# TK510_Signalbakplan.net
KiCad netlist of a schematic drawn in Altium Designer
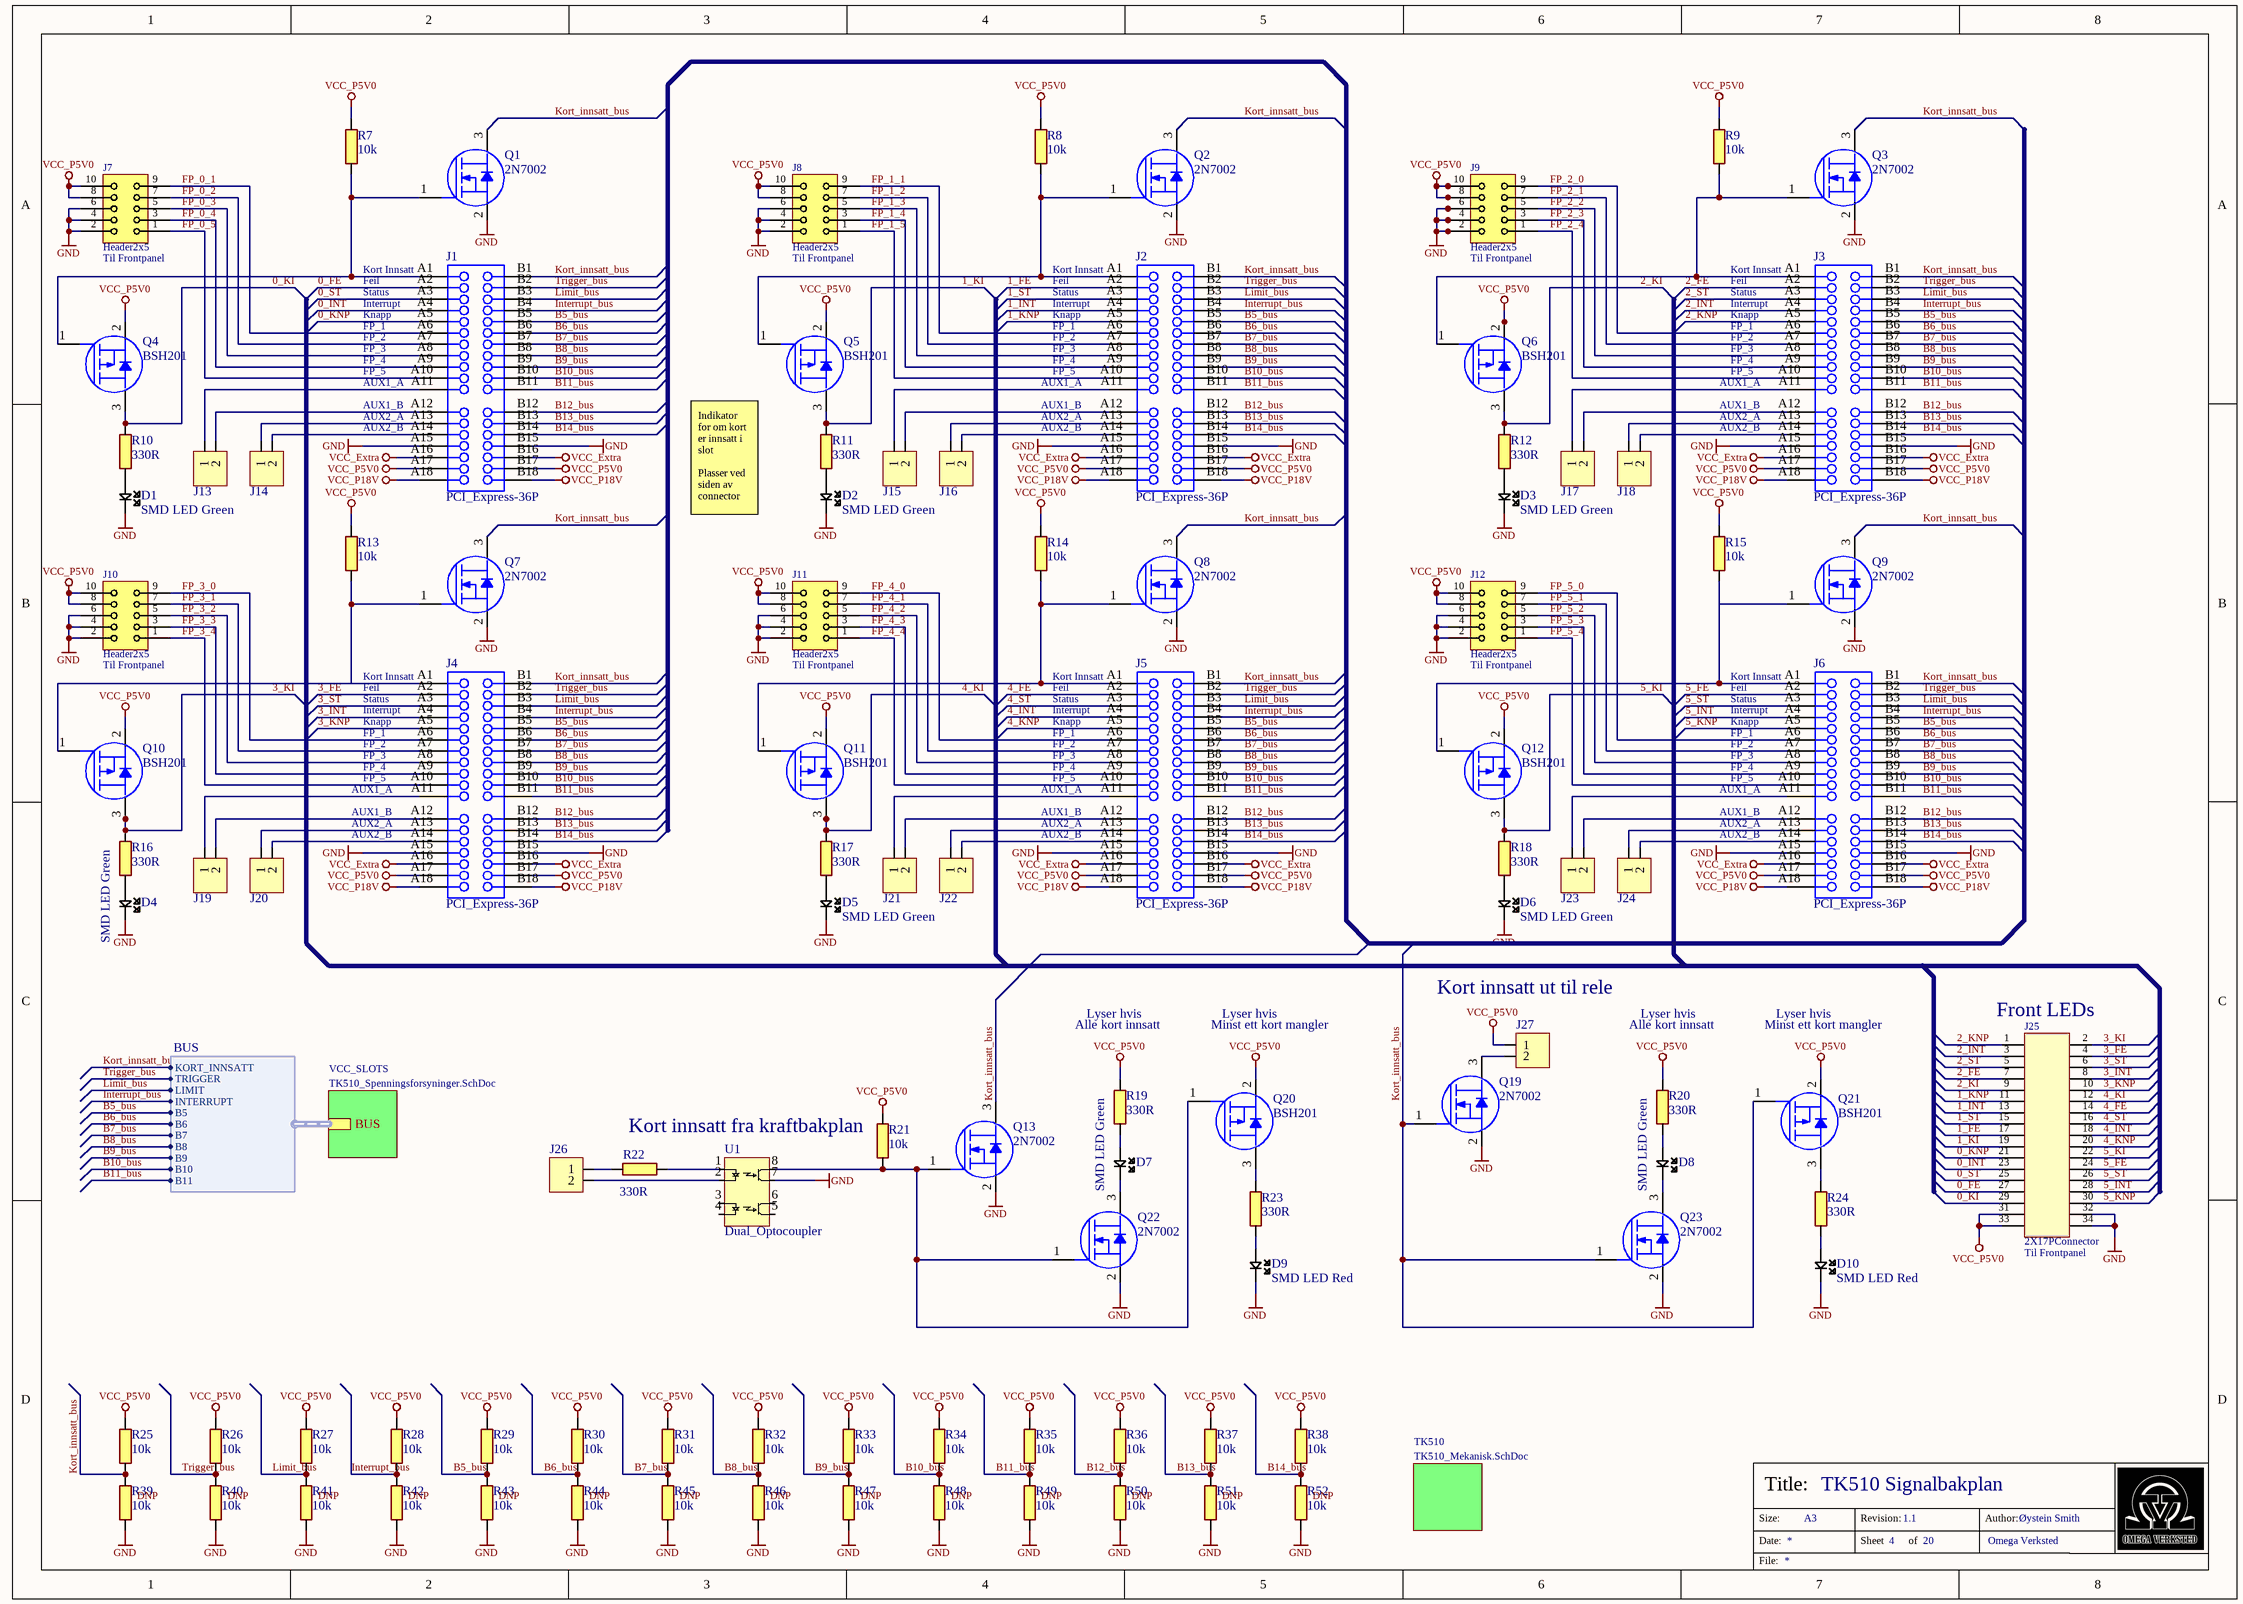
[diagram p0: TK510_Signalbakplan.SchDoc]

(export (version "E")
  (design (tool "Eeschema 10.0.6"))
  (components
    (comp (ref "D1")
      (value "SMD LED Green")
      (footprint "I_LEDC0603(1608)_N")
      (description "SMD")
      (libsource (lib "OVLib_64") (part "LED"))
    )
    (comp (ref "D2")
      (value "SMD LED Green")
      (footprint "I_LEDC0603(1608)_N")
      (description "SMD")
      (libsource (lib "OVLib_64") (part "LED"))
    )
    (comp (ref "D3")
      (value "SMD LED Green")
      (footprint "I_LEDC0603(1608)_N")
      (description "SMD")
      (libsource (lib "OVLib_64") (part "LED"))
    )
    (comp (ref "D4")
      (value "SMD LED Green")
      (footprint "I_LEDC0603(1608)_N")
      (description "SMD")
      (libsource (lib "OVLib_64") (part "LED"))
    )
    (comp (ref "D5")
      (value "SMD LED Green")
      (footprint "I_LEDC0603(1608)_N")
      (description "SMD")
      (libsource (lib "OVLib_64") (part "LED"))
    )
    (comp (ref "D6")
      (value "SMD LED Green")
      (footprint "I_LEDC0603(1608)_N")
      (description "SMD")
      (libsource (lib "OVLib_64") (part "LED"))
    )
    (comp (ref "D7")
      (value "SMD LED Green")
      (footprint "I_LEDC0603(1608)_N")
      (description "SMD")
      (libsource (lib "OVLib_64") (part "LED"))
    )
    (comp (ref "D8")
      (value "SMD LED Green")
      (footprint "I_LEDC0603(1608)_N")
      (description "SMD")
      (libsource (lib "OVLib_64") (part "LED"))
    )
    (comp (ref "D9")
      (value "SMD LED Red")
      (footprint "I_LEDC0603(1608)_N")
      (description "SMD")
      (libsource (lib "OVLib_64") (part "LED"))
    )
    (comp (ref "D10")
      (value "SMD LED Red")
      (footprint "I_LEDC0603(1608)_N")
      (description "SMD")
      (libsource (lib "OVLib_64") (part "LED"))
    )
    (comp (ref "J1")
      (value "PCI_Express-36P")
      (footprint "PCI_Express-36P")
      (libsource (lib "OVLib_64") (part "PCI_Express-36P"))
    )
    (comp (ref "J2")
      (value "PCI_Express-36P")
      (footprint "PCI_Express-36P")
      (libsource (lib "OVLib_64") (part "PCI_Express-36P"))
    )
    (comp (ref "J3")
      (value "PCI_Express-36P")
      (footprint "PCI_Express-36P")
      (libsource (lib "OVLib_64") (part "PCI_Express-36P"))
    )
    (comp (ref "J4")
      (value "PCI_Express-36P")
      (footprint "PCI_Express-36P")
      (libsource (lib "OVLib_64") (part "PCI_Express-36P"))
    )
    (comp (ref "J5")
      (value "PCI_Express-36P")
      (footprint "PCI_Express-36P")
      (libsource (lib "OVLib_64") (part "PCI_Express-36P"))
    )
    (comp (ref "J6")
      (value "PCI_Express-36P")
      (footprint "PCI_Express-36P")
      (libsource (lib "OVLib_64") (part "PCI_Express-36P"))
    )
    (comp (ref "J7")
      (value "Header2x5")
      (footprint "HDRV10W64P254_2X5_2030X900X900B")
      (description "Header")
      (libsource (lib "OVLib_64") (part "Header2x5"))
    )
    (comp (ref "J8")
      (value "Header2x5")
      (footprint "HDRV10W64P254_2X5_2030X900X900B")
      (description "Header")
      (libsource (lib "OVLib_64") (part "Header2x5"))
    )
    (comp (ref "J9")
      (value "Header2x5")
      (footprint "HDRV10W64P254_2X5_2030X900X900B")
      (description "Header")
      (libsource (lib "OVLib_64") (part "Header2x5"))
    )
    (comp (ref "J10")
      (value "Header2x5")
      (footprint "HDRV10W64P254_2X5_2030X900X900B")
      (description "Header")
      (libsource (lib "OVLib_64") (part "Header2x5"))
    )
    (comp (ref "J11")
      (value "Header2x5")
      (footprint "HDRV10W64P254_2X5_2030X900X900B")
      (description "Header")
      (libsource (lib "OVLib_64") (part "Header2x5"))
    )
    (comp (ref "J12")
      (value "Header2x5")
      (footprint "HDRV10W64P254_2X5_2030X900X900B")
      (description "Header")
      (libsource (lib "OVLib_64") (part "Header2x5"))
    )
    (comp (ref "J13")
      (value "B2B-XH-A (LF)(SN)")
      (footprint "JST_2P")
      (description "JST 2pin (pris pr. stk.)")
      (libsource (lib "OVLib_64") (part "2PConnector"))
    )
    (comp (ref "J14")
      (value "B2B-XH-A (LF)(SN)")
      (footprint "JST_2P")
      (description "JST 2pin (pris pr. stk.)")
      (libsource (lib "OVLib_64") (part "2PConnector"))
    )
    (comp (ref "J15")
      (value "B2B-XH-A (LF)(SN)")
      (footprint "JST_2P")
      (description "JST 2pin (pris pr. stk.)")
      (libsource (lib "OVLib_64") (part "2PConnector"))
    )
    (comp (ref "J16")
      (value "B2B-XH-A (LF)(SN)")
      (footprint "JST_2P")
      (description "JST 2pin (pris pr. stk.)")
      (libsource (lib "OVLib_64") (part "2PConnector"))
    )
    (comp (ref "J17")
      (value "B2B-XH-A (LF)(SN)")
      (footprint "JST_2P")
      (description "JST 2pin (pris pr. stk.)")
      (libsource (lib "OVLib_64") (part "2PConnector"))
    )
    (comp (ref "J18")
      (value "B2B-XH-A (LF)(SN)")
      (footprint "JST_2P")
      (description "JST 2pin (pris pr. stk.)")
      (libsource (lib "OVLib_64") (part "2PConnector"))
    )
    (comp (ref "J19")
      (value "B2B-XH-A (LF)(SN)")
      (footprint "JST_2P")
      (description "JST 2pin (pris pr. stk.)")
      (libsource (lib "OVLib_64") (part "2PConnector"))
    )
    (comp (ref "J20")
      (value "B2B-XH-A (LF)(SN)")
      (footprint "JST_2P")
      (description "JST 2pin (pris pr. stk.)")
      (libsource (lib "OVLib_64") (part "2PConnector"))
    )
    (comp (ref "J21")
      (value "B2B-XH-A (LF)(SN)")
      (footprint "JST_2P")
      (description "JST 2pin (pris pr. stk.)")
      (libsource (lib "OVLib_64") (part "2PConnector"))
    )
    (comp (ref "J22")
      (value "B2B-XH-A (LF)(SN)")
      (footprint "JST_2P")
      (description "JST 2pin (pris pr. stk.)")
      (libsource (lib "OVLib_64") (part "2PConnector"))
    )
    (comp (ref "J23")
      (value "B2B-XH-A (LF)(SN)")
      (footprint "JST_2P")
      (description "JST 2pin (pris pr. stk.)")
      (libsource (lib "OVLib_64") (part "2PConnector"))
    )
    (comp (ref "J24")
      (value "B2B-XH-A (LF)(SN)")
      (footprint "JST_2P")
      (description "JST 2pin (pris pr. stk.)")
      (libsource (lib "OVLib_64") (part "2PConnector"))
    )
    (comp (ref "J25")
      (value "2X17PConnector")
      (footprint "HDRV34W64P254_2X17_5070X900X900B")
      (description "Header")
      (libsource (lib "OVLib_64") (part "2X17PConnector"))
    )
    (comp (ref "J26")
      (value "B2B-XH-A (LF)(SN)")
      (footprint "JST_2P")
      (description "JST 2pin (pris pr. stk.)")
      (libsource (lib "") (part "2PConnector_2"))
    )
    (comp (ref "J27")
      (value "B2B-XH-A (LF)(SN)")
      (footprint "JST_2P")
      (description "JST 2pin (pris pr. stk.)")
      (libsource (lib "") (part "2PConnector_1"))
    )
    (comp (ref "Q1")
      (value "2N7002")
      (footprint "SOT23-3_N")
      (description "N-Channel MOSFET 300mA")
      (libsource (lib "OVLib_64") (part "MOSFET_N_GSD"))
    )
    (comp (ref "Q2")
      (value "2N7002")
      (footprint "SOT23-3_N")
      (description "N-Channel MOSFET 300mA")
      (libsource (lib "OVLib_64") (part "MOSFET_N_GSD"))
    )
    (comp (ref "Q3")
      (value "2N7002")
      (footprint "SOT23-3_N")
      (description "N-Channel MOSFET 300mA")
      (libsource (lib "") (part "MOSFET_N_GSD_1"))
    )
    (comp (ref "Q4")
      (value "BSH201")
      (footprint "SOT23-3_N")
      (description "P-Channel MOSFET 300mA")
      (libsource (lib "OVLib_64") (part "MOSFET_P_GSD"))
    )
    (comp (ref "Q5")
      (value "BSH201")
      (footprint "SOT23-3_N")
      (description "P-Channel MOSFET 300mA")
      (libsource (lib "OVLib_64") (part "MOSFET_P_GSD"))
    )
    (comp (ref "Q6")
      (value "BSH201")
      (footprint "SOT23-3_N")
      (description "P-Channel MOSFET 300mA")
      (libsource (lib "OVLib_64") (part "MOSFET_P_GSD"))
    )
    (comp (ref "Q7")
      (value "2N7002")
      (footprint "SOT23-3_N")
      (description "N-Channel MOSFET 300mA")
      (libsource (lib "OVLib_64") (part "MOSFET_N_GSD"))
    )
    (comp (ref "Q8")
      (value "2N7002")
      (footprint "SOT23-3_N")
      (description "N-Channel MOSFET 300mA")
      (libsource (lib "OVLib_64") (part "MOSFET_N_GSD"))
    )
    (comp (ref "Q9")
      (value "2N7002")
      (footprint "SOT23-3_N")
      (description "N-Channel MOSFET 300mA")
      (libsource (lib "") (part "MOSFET_N_GSD_1"))
    )
    (comp (ref "Q10")
      (value "BSH201")
      (footprint "SOT23-3_N")
      (description "P-Channel MOSFET 300mA")
      (libsource (lib "OVLib_64") (part "MOSFET_P_GSD"))
    )
    (comp (ref "Q11")
      (value "BSH201")
      (footprint "SOT23-3_N")
      (description "P-Channel MOSFET 300mA")
      (libsource (lib "OVLib_64") (part "MOSFET_P_GSD"))
    )
    (comp (ref "Q12")
      (value "BSH201")
      (footprint "SOT23-3_N")
      (description "P-Channel MOSFET 300mA")
      (libsource (lib "OVLib_64") (part "MOSFET_P_GSD"))
    )
    (comp (ref "Q13")
      (value "2N7002")
      (footprint "SOT23-3_N")
      (description "N-Channel MOSFET 300mA")
      (libsource (lib "OVLib_64") (part "MOSFET_N_GSD"))
    )
    (comp (ref "Q19")
      (value "2N7002")
      (footprint "SOT23-3_N")
      (description "N-Channel MOSFET 300mA")
      (libsource (lib "OVLib_64") (part "MOSFET_N_GSD"))
    )
    (comp (ref "Q20")
      (value "BSH201")
      (footprint "SOT23-3_N")
      (description "P-Channel MOSFET 300mA")
      (libsource (lib "") (part "MOSFET_P_GSD_1"))
    )
    (comp (ref "Q21")
      (value "BSH201")
      (footprint "SOT23-3_N")
      (description "P-Channel MOSFET 300mA")
      (libsource (lib "") (part "MOSFET_P_GSD_1"))
    )
    (comp (ref "Q22")
      (value "2N7002")
      (footprint "SOT23-3_N")
      (description "N-Channel MOSFET 300mA")
      (libsource (lib "OVLib_64") (part "MOSFET_N_GSD"))
    )
    (comp (ref "Q23")
      (value "2N7002")
      (footprint "SOT23-3_N")
      (description "N-Channel MOSFET 300mA")
      (libsource (lib "OVLib_64") (part "MOSFET_N_GSD"))
    )
    (comp (ref "R7")
      (value "10k")
      (footprint "RESC0603(1608)_N")
      (description "0.1W 1% Thick film resistor")
      (libsource (lib "OVLib_64") (part "Resistor2"))
    )
    (comp (ref "R8")
      (value "10k")
      (footprint "RESC0603(1608)_N")
      (description "0.1W 1% Thick film resistor")
      (libsource (lib "OVLib_64") (part "Resistor2"))
    )
    (comp (ref "R9")
      (value "10k")
      (footprint "RESC0603(1608)_N")
      (description "0.1W 1% Thick film resistor")
      (libsource (lib "OVLib_64") (part "Resistor2"))
    )
    (comp (ref "R10")
      (value "330R")
      (footprint "RESC0603(1608)_N")
      (description "0.1W 1% Thick film resistor")
      (libsource (lib "OVLib_64") (part "Resistor2"))
    )
    (comp (ref "R11")
      (value "330R")
      (footprint "RESC0603(1608)_N")
      (description "0.1W 1% Thick film resistor")
      (libsource (lib "OVLib_64") (part "Resistor2"))
    )
    (comp (ref "R12")
      (value "330R")
      (footprint "RESC0603(1608)_N")
      (description "0.1W 1% Thick film resistor")
      (libsource (lib "OVLib_64") (part "Resistor2"))
    )
    (comp (ref "R13")
      (value "10k")
      (footprint "RESC0603(1608)_N")
      (description "0.1W 1% Thick film resistor")
      (libsource (lib "OVLib_64") (part "Resistor2"))
    )
    (comp (ref "R14")
      (value "10k")
      (footprint "RESC0603(1608)_N")
      (description "0.1W 1% Thick film resistor")
      (libsource (lib "OVLib_64") (part "Resistor2"))
    )
    (comp (ref "R15")
      (value "10k")
      (footprint "RESC0603(1608)_N")
      (description "0.1W 1% Thick film resistor")
      (libsource (lib "OVLib_64") (part "Resistor2"))
    )
    (comp (ref "R16")
      (value "330R")
      (footprint "RESC0603(1608)_N")
      (description "0.1W 1% Thick film resistor")
      (libsource (lib "OVLib_64") (part "Resistor2"))
    )
    (comp (ref "R17")
      (value "330R")
      (footprint "RESC0603(1608)_N")
      (description "0.1W 1% Thick film resistor")
      (libsource (lib "OVLib_64") (part "Resistor2"))
    )
    (comp (ref "R18")
      (value "330R")
      (footprint "RESC0603(1608)_N")
      (description "0.1W 1% Thick film resistor")
      (libsource (lib "OVLib_64") (part "Resistor2"))
    )
    (comp (ref "R19")
      (value "330R")
      (footprint "RESC0603(1608)_N")
      (description "0.1W 1% Thick film resistor")
      (libsource (lib "OVLib_64") (part "Resistor2"))
    )
    (comp (ref "R20")
      (value "330R")
      (footprint "RESC0603(1608)_N")
      (description "0.1W 1% Thick film resistor")
      (libsource (lib "OVLib_64") (part "Resistor2"))
    )
    (comp (ref "R21")
      (value "10k")
      (footprint "RESC0603(1608)_N")
      (description "0.1W 1% Thick film resistor")
      (libsource (lib "OVLib_64") (part "Resistor2"))
    )
    (comp (ref "R22")
      (value "330R")
      (footprint "RESC0603(1608)_N")
      (description "0.1W 1% Thick film resistor")
      (libsource (lib "") (part "Resistor2_1"))
    )
    (comp (ref "R23")
      (value "330R")
      (footprint "RESC0603(1608)_N")
      (description "0.1W 1% Thick film resistor")
      (libsource (lib "OVLib_64") (part "Resistor2"))
    )
    (comp (ref "R24")
      (value "330R")
      (footprint "RESC0603(1608)_N")
      (description "0.1W 1% Thick film resistor")
      (libsource (lib "OVLib_64") (part "Resistor2"))
    )
    (comp (ref "R25")
      (value "10k")
      (footprint "RESC0603(1608)_N")
      (description "0.1W 1% Thick film resistor")
      (libsource (lib "OVLib_64") (part "Resistor2"))
    )
    (comp (ref "R26")
      (value "10k")
      (footprint "RESC0603(1608)_N")
      (description "0.1W 1% Thick film resistor")
      (libsource (lib "OVLib_64") (part "Resistor2"))
    )
    (comp (ref "R27")
      (value "10k")
      (footprint "RESC0603(1608)_N")
      (description "0.1W 1% Thick film resistor")
      (libsource (lib "OVLib_64") (part "Resistor2"))
    )
    (comp (ref "R28")
      (value "10k")
      (footprint "RESC0603(1608)_N")
      (description "0.1W 1% Thick film resistor")
      (libsource (lib "OVLib_64") (part "Resistor2"))
    )
    (comp (ref "R29")
      (value "10k")
      (footprint "RESC0603(1608)_N")
      (description "0.1W 1% Thick film resistor")
      (libsource (lib "OVLib_64") (part "Resistor2"))
    )
    (comp (ref "R30")
      (value "10k")
      (footprint "RESC0603(1608)_N")
      (description "0.1W 1% Thick film resistor")
      (libsource (lib "OVLib_64") (part "Resistor2"))
    )
    (comp (ref "R31")
      (value "10k")
      (footprint "RESC0603(1608)_N")
      (description "0.1W 1% Thick film resistor")
      (libsource (lib "OVLib_64") (part "Resistor2"))
    )
    (comp (ref "R32")
      (value "10k")
      (footprint "RESC0603(1608)_N")
      (description "0.1W 1% Thick film resistor")
      (libsource (lib "OVLib_64") (part "Resistor2"))
    )
    (comp (ref "R33")
      (value "10k")
      (footprint "RESC0603(1608)_N")
      (description "0.1W 1% Thick film resistor")
      (libsource (lib "OVLib_64") (part "Resistor2"))
    )
    (comp (ref "R34")
      (value "10k")
      (footprint "RESC0603(1608)_N")
      (description "0.1W 1% Thick film resistor")
      (libsource (lib "OVLib_64") (part "Resistor2"))
    )
    (comp (ref "R35")
      (value "10k")
      (footprint "RESC0603(1608)_N")
      (description "0.1W 1% Thick film resistor")
      (libsource (lib "OVLib_64") (part "Resistor2"))
    )
    (comp (ref "R36")
      (value "10k")
      (footprint "RESC0603(1608)_N")
      (description "0.1W 1% Thick film resistor")
      (libsource (lib "OVLib_64") (part "Resistor2"))
    )
    (comp (ref "R37")
      (value "10k")
      (footprint "RESC0603(1608)_N")
      (description "0.1W 1% Thick film resistor")
      (libsource (lib "OVLib_64") (part "Resistor2"))
    )
    (comp (ref "R38")
      (value "10k")
      (footprint "RESC0603(1608)_N")
      (description "0.1W 1% Thick film resistor")
      (libsource (lib "OVLib_64") (part "Resistor2"))
    )
    (comp (ref "R39")
      (value "10k")
      (footprint "RESC0603(1608)_N")
      (description "0.1W 1% Thick film resistor")
      (libsource (lib "OVLib_64") (part "Resistor2"))
    )
    (comp (ref "R40")
      (value "10k")
      (footprint "RESC0603(1608)_N")
      (description "0.1W 1% Thick film resistor")
      (libsource (lib "OVLib_64") (part "Resistor2"))
    )
    (comp (ref "R41")
      (value "10k")
      (footprint "RESC0603(1608)_N")
      (description "0.1W 1% Thick film resistor")
      (libsource (lib "OVLib_64") (part "Resistor2"))
    )
    (comp (ref "R42")
      (value "10k")
      (footprint "RESC0603(1608)_N")
      (description "0.1W 1% Thick film resistor")
      (libsource (lib "OVLib_64") (part "Resistor2"))
    )
    (comp (ref "R43")
      (value "10k")
      (footprint "RESC0603(1608)_N")
      (description "0.1W 1% Thick film resistor")
      (libsource (lib "OVLib_64") (part "Resistor2"))
    )
    (comp (ref "R44")
      (value "10k")
      (footprint "RESC0603(1608)_N")
      (description "0.1W 1% Thick film resistor")
      (libsource (lib "OVLib_64") (part "Resistor2"))
    )
    (comp (ref "R45")
      (value "10k")
      (footprint "RESC0603(1608)_N")
      (description "0.1W 1% Thick film resistor")
      (libsource (lib "OVLib_64") (part "Resistor2"))
    )
    (comp (ref "R46")
      (value "10k")
      (footprint "RESC0603(1608)_N")
      (description "0.1W 1% Thick film resistor")
      (libsource (lib "OVLib_64") (part "Resistor2"))
    )
    (comp (ref "R47")
      (value "10k")
      (footprint "RESC0603(1608)_N")
      (description "0.1W 1% Thick film resistor")
      (libsource (lib "OVLib_64") (part "Resistor2"))
    )
    (comp (ref "R48")
      (value "10k")
      (footprint "RESC0603(1608)_N")
      (description "0.1W 1% Thick film resistor")
      (libsource (lib "OVLib_64") (part "Resistor2"))
    )
    (comp (ref "R49")
      (value "10k")
      (footprint "RESC0603(1608)_N")
      (description "0.1W 1% Thick film resistor")
      (libsource (lib "OVLib_64") (part "Resistor2"))
    )
    (comp (ref "R50")
      (value "10k")
      (footprint "RESC0603(1608)_N")
      (description "0.1W 1% Thick film resistor")
      (libsource (lib "OVLib_64") (part "Resistor2"))
    )
    (comp (ref "R51")
      (value "10k")
      (footprint "RESC0603(1608)_N")
      (description "0.1W 1% Thick film resistor")
      (libsource (lib "OVLib_64") (part "Resistor2"))
    )
    (comp (ref "R52")
      (value "10k")
      (footprint "RESC0603(1608)_N")
      (description "0.1W 1% Thick film resistor")
      (libsource (lib "OVLib_64") (part "Resistor2"))
    )
    (comp (ref "U1")
      (value "Dual_Optocoupler")
      (footprint "SOIC127P590X363-8N")
      (description "Dual Optocoupler")
      (libsource (lib "OVLib_64") (part "Dual_Optocoupler"))
    )
  )
  (nets
    (net (code "2") (name "/0_FE") (class "Default")
      (node (ref "J1") (pin "A2") (pinfunction "A2_A2") (pintype "passive"))
      (node (ref "J25") (pin "27") (pinfunction "27_27") (pintype "passive"))
    )
    (net (code "3") (name "/0_INT") (class "Default")
      (node (ref "J1") (pin "A4") (pinfunction "A4_A4") (pintype "passive"))
      (node (ref "J25") (pin "23") (pinfunction "23_23") (pintype "passive"))
    )
    (net (code "4") (name "/0_KI") (class "Default")
      (node (ref "J25") (pin "29") (pinfunction "29_29") (pintype "passive"))
      (node (ref "Q4") (pin "3") (pinfunction "Drain_3") (pintype "passive"))
      (node (ref "R10") (pin "2") (pinfunction "2_2") (pintype "passive"))
    )
    (net (code "5") (name "/0_KNP") (class "Default")
      (node (ref "J1") (pin "A5") (pinfunction "A5_A5") (pintype "passive"))
      (node (ref "J25") (pin "21") (pinfunction "21_21") (pintype "passive"))
    )
    (net (code "6") (name "/0_ST") (class "Default")
      (node (ref "J1") (pin "A3") (pinfunction "A3_A3") (pintype "passive"))
      (node (ref "J25") (pin "25") (pinfunction "25_25") (pintype "passive"))
    )
    (net (code "7") (name "/1_FE") (class "Default")
      (node (ref "J2") (pin "A2") (pinfunction "A2_A2") (pintype "passive"))
      (node (ref "J25") (pin "17") (pinfunction "17_17") (pintype "passive"))
    )
    (net (code "8") (name "/1_INT") (class "Default")
      (node (ref "J2") (pin "A4") (pinfunction "A4_A4") (pintype "passive"))
      (node (ref "J25") (pin "13") (pinfunction "13_13") (pintype "passive"))
    )
    (net (code "9") (name "/1_KI") (class "Default")
      (node (ref "J25") (pin "19") (pinfunction "19_19") (pintype "passive"))
      (node (ref "Q5") (pin "3") (pinfunction "Drain_3") (pintype "passive"))
      (node (ref "R11") (pin "2") (pinfunction "2_2") (pintype "passive"))
    )
    (net (code "10") (name "/1_KNP") (class "Default")
      (node (ref "J2") (pin "A5") (pinfunction "A5_A5") (pintype "passive"))
      (node (ref "J25") (pin "11") (pinfunction "11_11") (pintype "passive"))
    )
    (net (code "11") (name "/1_ST") (class "Default")
      (node (ref "J2") (pin "A3") (pinfunction "A3_A3") (pintype "passive"))
      (node (ref "J25") (pin "15") (pinfunction "15_15") (pintype "passive"))
    )
    (net (code "12") (name "/2_FE") (class "Default")
      (node (ref "J25") (pin "7") (pinfunction "7_7") (pintype "passive"))
      (node (ref "J3") (pin "A2") (pinfunction "A2_A2") (pintype "passive"))
    )
    (net (code "13") (name "/2_INT") (class "Default")
      (node (ref "J25") (pin "3") (pinfunction "3_3") (pintype "passive"))
      (node (ref "J3") (pin "A4") (pinfunction "A4_A4") (pintype "passive"))
    )
    (net (code "14") (name "/2_KI") (class "Default")
      (node (ref "J25") (pin "9") (pinfunction "9_9") (pintype "passive"))
      (node (ref "Q6") (pin "3") (pinfunction "Drain_3") (pintype "passive"))
      (node (ref "R12") (pin "2") (pinfunction "2_2") (pintype "passive"))
    )
    (net (code "15") (name "/2_KNP") (class "Default")
      (node (ref "J25") (pin "1") (pinfunction "1_1") (pintype "passive"))
      (node (ref "J3") (pin "A5") (pinfunction "A5_A5") (pintype "passive"))
    )
    (net (code "16") (name "/2_ST") (class "Default")
      (node (ref "J25") (pin "5") (pinfunction "5_5") (pintype "passive"))
      (node (ref "J3") (pin "A3") (pinfunction "A3_A3") (pintype "passive"))
    )
    (net (code "17") (name "/3_FE") (class "Default")
      (node (ref "J25") (pin "4") (pinfunction "4_4") (pintype "passive"))
      (node (ref "J4") (pin "A2") (pinfunction "A2_A2") (pintype "passive"))
    )
    (net (code "18") (name "/3_INT") (class "Default")
      (node (ref "J25") (pin "8") (pinfunction "8_8") (pintype "passive"))
      (node (ref "J4") (pin "A4") (pinfunction "A4_A4") (pintype "passive"))
    )
    (net (code "19") (name "/3_KI") (class "Default")
      (node (ref "J25") (pin "2") (pinfunction "2_2") (pintype "passive"))
      (node (ref "Q10") (pin "3") (pinfunction "Drain_3") (pintype "passive"))
      (node (ref "R16") (pin "2") (pinfunction "2_2") (pintype "passive"))
    )
    (net (code "20") (name "/3_KNP") (class "Default")
      (node (ref "J25") (pin "10") (pinfunction "10_10") (pintype "passive"))
      (node (ref "J4") (pin "A5") (pinfunction "A5_A5") (pintype "passive"))
    )
    (net (code "21") (name "/3_ST") (class "Default")
      (node (ref "J25") (pin "6") (pinfunction "6_6") (pintype "passive"))
      (node (ref "J4") (pin "A3") (pinfunction "A3_A3") (pintype "passive"))
    )
    (net (code "22") (name "/4_FE") (class "Default")
      (node (ref "J25") (pin "14") (pinfunction "14_14") (pintype "passive"))
      (node (ref "J5") (pin "A2") (pinfunction "A2_A2") (pintype "passive"))
    )
    (net (code "23") (name "/4_INT") (class "Default")
      (node (ref "J25") (pin "18") (pinfunction "18_18") (pintype "passive"))
      (node (ref "J5") (pin "A4") (pinfunction "A4_A4") (pintype "passive"))
    )
    (net (code "24") (name "/4_KI") (class "Default")
      (node (ref "J25") (pin "12") (pinfunction "12_12") (pintype "passive"))
      (node (ref "Q11") (pin "3") (pinfunction "Drain_3") (pintype "passive"))
      (node (ref "R17") (pin "2") (pinfunction "2_2") (pintype "passive"))
    )
    (net (code "25") (name "/4_KNP") (class "Default")
      (node (ref "J25") (pin "20") (pinfunction "20_20") (pintype "passive"))
      (node (ref "J5") (pin "A5") (pinfunction "A5_A5") (pintype "passive"))
    )
    (net (code "26") (name "/4_ST") (class "Default")
      (node (ref "J25") (pin "16") (pinfunction "16_16") (pintype "passive"))
      (node (ref "J5") (pin "A3") (pinfunction "A3_A3") (pintype "passive"))
    )
    (net (code "27") (name "/5_FE") (class "Default")
      (node (ref "J25") (pin "24") (pinfunction "24_24") (pintype "passive"))
      (node (ref "J6") (pin "A2") (pinfunction "A2_A2") (pintype "passive"))
    )
    (net (code "28") (name "/5_INT") (class "Default")
      (node (ref "J25") (pin "28") (pinfunction "28_28") (pintype "passive"))
      (node (ref "J6") (pin "A4") (pinfunction "A4_A4") (pintype "passive"))
    )
    (net (code "29") (name "/5_KI") (class "Default")
      (node (ref "J25") (pin "22") (pinfunction "22_22") (pintype "passive"))
      (node (ref "Q12") (pin "3") (pinfunction "Drain_3") (pintype "passive"))
      (node (ref "R18") (pin "2") (pinfunction "2_2") (pintype "passive"))
    )
    (net (code "30") (name "/5_KNP") (class "Default")
      (node (ref "J25") (pin "30") (pinfunction "30_30") (pintype "passive"))
      (node (ref "J6") (pin "A5") (pinfunction "A5_A5") (pintype "passive"))
    )
    (net (code "31") (name "/5_ST") (class "Default")
      (node (ref "J25") (pin "26") (pinfunction "26_26") (pintype "passive"))
      (node (ref "J6") (pin "A3") (pinfunction "A3_A3") (pintype "passive"))
    )
    (net (code "32") (name "/B5_bus") (class "Default")
      (node (ref "J1") (pin "B5") (pinfunction "B5_B5") (pintype "passive"))
      (node (ref "J2") (pin "B5") (pinfunction "B5_B5") (pintype "passive"))
      (node (ref "J3") (pin "B5") (pinfunction "B5_B5") (pintype "passive"))
      (node (ref "J4") (pin "B5") (pinfunction "B5_B5") (pintype "passive"))
      (node (ref "J5") (pin "B5") (pinfunction "B5_B5") (pintype "passive"))
      (node (ref "J6") (pin "B5") (pinfunction "B5_B5") (pintype "passive"))
      (node (ref "R29") (pin "1") (pinfunction "1_1") (pintype "passive"))
      (node (ref "R43") (pin "2") (pinfunction "2_2") (pintype "passive"))
    )
    (net (code "33") (name "/B6_bus") (class "Default")
      (node (ref "J1") (pin "B6") (pinfunction "B6_B6") (pintype "passive"))
      (node (ref "J2") (pin "B6") (pinfunction "B6_B6") (pintype "passive"))
      (node (ref "J3") (pin "B6") (pinfunction "B6_B6") (pintype "passive"))
      (node (ref "J4") (pin "B6") (pinfunction "B6_B6") (pintype "passive"))
      (node (ref "J5") (pin "B6") (pinfunction "B6_B6") (pintype "passive"))
      (node (ref "J6") (pin "B6") (pinfunction "B6_B6") (pintype "passive"))
      (node (ref "R30") (pin "1") (pinfunction "1_1") (pintype "passive"))
      (node (ref "R44") (pin "2") (pinfunction "2_2") (pintype "passive"))
    )
    (net (code "34") (name "/B7_bus") (class "Default")
      (node (ref "J1") (pin "B7") (pinfunction "B7_B7") (pintype "passive"))
      (node (ref "J2") (pin "B7") (pinfunction "B7_B7") (pintype "passive"))
      (node (ref "J3") (pin "B7") (pinfunction "B7_B7") (pintype "passive"))
      (node (ref "J4") (pin "B7") (pinfunction "B7_B7") (pintype "passive"))
      (node (ref "J5") (pin "B7") (pinfunction "B7_B7") (pintype "passive"))
      (node (ref "J6") (pin "B7") (pinfunction "B7_B7") (pintype "passive"))
      (node (ref "R31") (pin "1") (pinfunction "1_1") (pintype "passive"))
      (node (ref "R45") (pin "2") (pinfunction "2_2") (pintype "passive"))
    )
    (net (code "35") (name "/B8_bus") (class "Default")
      (node (ref "J1") (pin "B8") (pinfunction "B8_B8") (pintype "passive"))
      (node (ref "J2") (pin "B8") (pinfunction "B8_B8") (pintype "passive"))
      (node (ref "J3") (pin "B8") (pinfunction "B8_B8") (pintype "passive"))
      (node (ref "J4") (pin "B8") (pinfunction "B8_B8") (pintype "passive"))
      (node (ref "J5") (pin "B8") (pinfunction "B8_B8") (pintype "passive"))
      (node (ref "J6") (pin "B8") (pinfunction "B8_B8") (pintype "passive"))
      (node (ref "R32") (pin "1") (pinfunction "1_1") (pintype "passive"))
      (node (ref "R46") (pin "2") (pinfunction "2_2") (pintype "passive"))
    )
    (net (code "36") (name "/B9_bus") (class "Default")
      (node (ref "J1") (pin "B9") (pinfunction "B9_B9") (pintype "passive"))
      (node (ref "J2") (pin "B9") (pinfunction "B9_B9") (pintype "passive"))
      (node (ref "J3") (pin "B9") (pinfunction "B9_B9") (pintype "passive"))
      (node (ref "J4") (pin "B9") (pinfunction "B9_B9") (pintype "passive"))
      (node (ref "J5") (pin "B9") (pinfunction "B9_B9") (pintype "passive"))
      (node (ref "J6") (pin "B9") (pinfunction "B9_B9") (pintype "passive"))
      (node (ref "R33") (pin "1") (pinfunction "1_1") (pintype "passive"))
      (node (ref "R47") (pin "2") (pinfunction "2_2") (pintype "passive"))
    )
    (net (code "37") (name "/B10_bus") (class "Default")
      (node (ref "J1") (pin "B10") (pinfunction "B10_B10") (pintype "passive"))
      (node (ref "J2") (pin "B10") (pinfunction "B10_B10") (pintype "passive"))
      (node (ref "J3") (pin "B10") (pinfunction "B10_B10") (pintype "passive"))
      (node (ref "J4") (pin "B10") (pinfunction "B10_B10") (pintype "passive"))
      (node (ref "J5") (pin "B10") (pinfunction "B10_B10") (pintype "passive"))
      (node (ref "J6") (pin "B10") (pinfunction "B10_B10") (pintype "passive"))
      (node (ref "R34") (pin "1") (pinfunction "1_1") (pintype "passive"))
      (node (ref "R48") (pin "2") (pinfunction "2_2") (pintype "passive"))
    )
    (net (code "38") (name "/B11_bus") (class "Default")
      (node (ref "J1") (pin "B11") (pinfunction "B11_B11") (pintype "passive"))
      (node (ref "J2") (pin "B11") (pinfunction "B11_B11") (pintype "passive"))
      (node (ref "J3") (pin "B11") (pinfunction "B11_B11") (pintype "passive"))
      (node (ref "J4") (pin "B11") (pinfunction "B11_B11") (pintype "passive"))
      (node (ref "J5") (pin "B11") (pinfunction "B11_B11") (pintype "passive"))
      (node (ref "J6") (pin "B11") (pinfunction "B11_B11") (pintype "passive"))
      (node (ref "R35") (pin "1") (pinfunction "1_1") (pintype "passive"))
      (node (ref "R49") (pin "2") (pinfunction "2_2") (pintype "passive"))
    )
    (net (code "39") (name "/B12_bus") (class "Default")
      (node (ref "J1") (pin "B12") (pinfunction "B12_B12") (pintype "passive"))
      (node (ref "J2") (pin "B12") (pinfunction "B12_B12") (pintype "passive"))
      (node (ref "J3") (pin "B12") (pinfunction "B12_B12") (pintype "passive"))
      (node (ref "J4") (pin "B12") (pinfunction "B12_B12") (pintype "passive"))
      (node (ref "J5") (pin "B12") (pinfunction "B12_B12") (pintype "passive"))
      (node (ref "J6") (pin "B12") (pinfunction "B12_B12") (pintype "passive"))
      (node (ref "R36") (pin "1") (pinfunction "1_1") (pintype "passive"))
      (node (ref "R50") (pin "2") (pinfunction "2_2") (pintype "passive"))
    )
    (net (code "40") (name "/B13_bus") (class "Default")
      (node (ref "J1") (pin "B13") (pinfunction "B13_B13") (pintype "passive"))
      (node (ref "J2") (pin "B13") (pinfunction "B13_B13") (pintype "passive"))
      (node (ref "J3") (pin "B13") (pinfunction "B13_B13") (pintype "passive"))
      (node (ref "J4") (pin "B13") (pinfunction "B13_B13") (pintype "passive"))
      (node (ref "J5") (pin "B13") (pinfunction "B13_B13") (pintype "passive"))
      (node (ref "J6") (pin "B13") (pinfunction "B13_B13") (pintype "passive"))
      (node (ref "R37") (pin "1") (pinfunction "1_1") (pintype "passive"))
      (node (ref "R51") (pin "2") (pinfunction "2_2") (pintype "passive"))
    )
    (net (code "41") (name "/B14_bus") (class "Default")
      (node (ref "J1") (pin "B14") (pinfunction "B14_B14") (pintype "passive"))
      (node (ref "J2") (pin "B14") (pinfunction "B14_B14") (pintype "passive"))
      (node (ref "J3") (pin "B14") (pinfunction "B14_B14") (pintype "passive"))
      (node (ref "J4") (pin "B14") (pinfunction "B14_B14") (pintype "passive"))
      (node (ref "J5") (pin "B14") (pinfunction "B14_B14") (pintype "passive"))
      (node (ref "J6") (pin "B14") (pinfunction "B14_B14") (pintype "passive"))
      (node (ref "R38") (pin "1") (pinfunction "1_1") (pintype "passive"))
      (node (ref "R52") (pin "2") (pinfunction "2_2") (pintype "passive"))
    )
    (net (code "42") (name "/FP_0_1") (class "Default")
      (node (ref "J1") (pin "A6") (pinfunction "A6_A6") (pintype "passive"))
      (node (ref "J7") (pin "9") (pinfunction "9_9") (pintype "passive"))
    )
    (net (code "43") (name "/FP_0_2") (class "Default")
      (node (ref "J1") (pin "A7") (pinfunction "A7_A7") (pintype "passive"))
      (node (ref "J7") (pin "7") (pinfunction "7_7") (pintype "passive"))
    )
    (net (code "44") (name "/FP_0_3") (class "Default")
      (node (ref "J1") (pin "A8") (pinfunction "A8_A8") (pintype "passive"))
      (node (ref "J7") (pin "5") (pinfunction "5_5") (pintype "passive"))
    )
    (net (code "45") (name "/FP_0_4") (class "Default")
      (node (ref "J1") (pin "A9") (pinfunction "A9_A9") (pintype "passive"))
      (node (ref "J7") (pin "3") (pinfunction "3_3") (pintype "passive"))
    )
    (net (code "46") (name "/FP_0_5") (class "Default")
      (node (ref "J1") (pin "A10") (pinfunction "A10_A10") (pintype "passive"))
      (node (ref "J7") (pin "1") (pinfunction "1_1") (pintype "passive"))
    )
    (net (code "47") (name "/FP_1_1") (class "Default")
      (node (ref "J2") (pin "A6") (pinfunction "A6_A6") (pintype "passive"))
      (node (ref "J8") (pin "9") (pinfunction "9_9") (pintype "passive"))
    )
    (net (code "48") (name "/FP_1_2") (class "Default")
      (node (ref "J2") (pin "A7") (pinfunction "A7_A7") (pintype "passive"))
      (node (ref "J8") (pin "7") (pinfunction "7_7") (pintype "passive"))
    )
    (net (code "49") (name "/FP_1_3") (class "Default")
      (node (ref "J2") (pin "A8") (pinfunction "A8_A8") (pintype "passive"))
      (node (ref "J8") (pin "5") (pinfunction "5_5") (pintype "passive"))
    )
    (net (code "50") (name "/FP_1_4") (class "Default")
      (node (ref "J2") (pin "A9") (pinfunction "A9_A9") (pintype "passive"))
      (node (ref "J8") (pin "3") (pinfunction "3_3") (pintype "passive"))
    )
    (net (code "51") (name "/FP_1_5") (class "Default")
      (node (ref "J2") (pin "A10") (pinfunction "A10_A10") (pintype "passive"))
      (node (ref "J8") (pin "1") (pinfunction "1_1") (pintype "passive"))
    )
    (net (code "52") (name "/FP_2_0") (class "Default")
      (node (ref "J3") (pin "A6") (pinfunction "A6_A6") (pintype "passive"))
      (node (ref "J9") (pin "9") (pinfunction "9_9") (pintype "passive"))
    )
    (net (code "53") (name "/FP_2_1") (class "Default")
      (node (ref "J3") (pin "A7") (pinfunction "A7_A7") (pintype "passive"))
      (node (ref "J9") (pin "7") (pinfunction "7_7") (pintype "passive"))
    )
    (net (code "54") (name "/FP_2_2") (class "Default")
      (node (ref "J3") (pin "A8") (pinfunction "A8_A8") (pintype "passive"))
      (node (ref "J9") (pin "5") (pinfunction "5_5") (pintype "passive"))
    )
    (net (code "55") (name "/FP_2_3") (class "Default")
      (node (ref "J3") (pin "A9") (pinfunction "A9_A9") (pintype "passive"))
      (node (ref "J9") (pin "3") (pinfunction "3_3") (pintype "passive"))
    )
    (net (code "56") (name "/FP_2_4") (class "Default")
      (node (ref "J3") (pin "A10") (pinfunction "A10_A10") (pintype "passive"))
      (node (ref "J9") (pin "1") (pinfunction "1_1") (pintype "passive"))
    )
    (net (code "57") (name "/FP_3_0") (class "Default")
      (node (ref "J10") (pin "9") (pinfunction "9_9") (pintype "passive"))
      (node (ref "J4") (pin "A6") (pinfunction "A6_A6") (pintype "passive"))
    )
    (net (code "58") (name "/FP_3_1") (class "Default")
      (node (ref "J10") (pin "7") (pinfunction "7_7") (pintype "passive"))
      (node (ref "J4") (pin "A7") (pinfunction "A7_A7") (pintype "passive"))
    )
    (net (code "59") (name "/FP_3_2") (class "Default")
      (node (ref "J10") (pin "5") (pinfunction "5_5") (pintype "passive"))
      (node (ref "J4") (pin "A8") (pinfunction "A8_A8") (pintype "passive"))
    )
    (net (code "60") (name "/FP_3_3") (class "Default")
      (node (ref "J10") (pin "3") (pinfunction "3_3") (pintype "passive"))
      (node (ref "J4") (pin "A9") (pinfunction "A9_A9") (pintype "passive"))
    )
    (net (code "61") (name "/FP_3_4") (class "Default")
      (node (ref "J10") (pin "1") (pinfunction "1_1") (pintype "passive"))
      (node (ref "J4") (pin "A10") (pinfunction "A10_A10") (pintype "passive"))
    )
    (net (code "62") (name "/FP_4_0") (class "Default")
      (node (ref "J11") (pin "9") (pinfunction "9_9") (pintype "passive"))
      (node (ref "J5") (pin "A6") (pinfunction "A6_A6") (pintype "passive"))
    )
    (net (code "63") (name "/FP_4_1") (class "Default")
      (node (ref "J11") (pin "7") (pinfunction "7_7") (pintype "passive"))
      (node (ref "J5") (pin "A7") (pinfunction "A7_A7") (pintype "passive"))
    )
    (net (code "64") (name "/FP_4_2") (class "Default")
      (node (ref "J11") (pin "5") (pinfunction "5_5") (pintype "passive"))
      (node (ref "J5") (pin "A8") (pinfunction "A8_A8") (pintype "passive"))
    )
    (net (code "65") (name "/FP_4_3") (class "Default")
      (node (ref "J11") (pin "3") (pinfunction "3_3") (pintype "passive"))
      (node (ref "J5") (pin "A9") (pinfunction "A9_A9") (pintype "passive"))
    )
    (net (code "66") (name "/FP_4_4") (class "Default")
      (node (ref "J11") (pin "1") (pinfunction "1_1") (pintype "passive"))
      (node (ref "J5") (pin "A10") (pinfunction "A10_A10") (pintype "passive"))
    )
    (net (code "67") (name "/FP_5_0") (class "Default")
      (node (ref "J12") (pin "9") (pinfunction "9_9") (pintype "passive"))
      (node (ref "J6") (pin "A6") (pinfunction "A6_A6") (pintype "passive"))
    )
    (net (code "68") (name "/FP_5_1") (class "Default")
      (node (ref "J12") (pin "7") (pinfunction "7_7") (pintype "passive"))
      (node (ref "J6") (pin "A7") (pinfunction "A7_A7") (pintype "passive"))
    )
    (net (code "69") (name "/FP_5_2") (class "Default")
      (node (ref "J12") (pin "5") (pinfunction "5_5") (pintype "passive"))
      (node (ref "J6") (pin "A8") (pinfunction "A8_A8") (pintype "passive"))
    )
    (net (code "70") (name "/FP_5_3") (class "Default")
      (node (ref "J12") (pin "3") (pinfunction "3_3") (pintype "passive"))
      (node (ref "J6") (pin "A9") (pinfunction "A9_A9") (pintype "passive"))
    )
    (net (code "71") (name "/FP_5_4") (class "Default")
      (node (ref "J12") (pin "1") (pinfunction "1_1") (pintype "passive"))
      (node (ref "J6") (pin "A10") (pinfunction "A10_A10") (pintype "passive"))
    )
    (net (code "72") (name "/Interrupt_bus") (class "Default")
      (node (ref "J1") (pin "B4") (pinfunction "B4_B4") (pintype "passive"))
      (node (ref "J2") (pin "B4") (pinfunction "B4_B4") (pintype "passive"))
      (node (ref "J3") (pin "B4") (pinfunction "B4_B4") (pintype "passive"))
      (node (ref "J4") (pin "B4") (pinfunction "B4_B4") (pintype "passive"))
      (node (ref "J5") (pin "B4") (pinfunction "B4_B4") (pintype "passive"))
      (node (ref "J6") (pin "B4") (pinfunction "B4_B4") (pintype "passive"))
      (node (ref "R28") (pin "1") (pinfunction "1_1") (pintype "passive"))
      (node (ref "R42") (pin "2") (pinfunction "2_2") (pintype "passive"))
    )
    (net (code "73") (name "/Kort_innsatt_bus") (class "Default")
      (node (ref "J1") (pin "B1") (pinfunction "B1_B1") (pintype "passive"))
      (node (ref "J2") (pin "B1") (pinfunction "B1_B1") (pintype "passive"))
      (node (ref "J3") (pin "B1") (pinfunction "B1_B1") (pintype "passive"))
      (node (ref "J4") (pin "B1") (pinfunction "B1_B1") (pintype "passive"))
      (node (ref "J5") (pin "B1") (pinfunction "B1_B1") (pintype "passive"))
      (node (ref "J6") (pin "B1") (pinfunction "B1_B1") (pintype "passive"))
      (node (ref "Q1") (pin "3") (pinfunction "Drain_3") (pintype "passive"))
      (node (ref "Q13") (pin "3") (pinfunction "Drain_3") (pintype "passive"))
      (node (ref "Q19") (pin "1") (pinfunction "Gate_1") (pintype "passive"))
      (node (ref "Q2") (pin "3") (pinfunction "Drain_3") (pintype "passive"))
      (node (ref "Q21") (pin "1") (pinfunction "Gate_1") (pintype "passive"))
      (node (ref "Q23") (pin "1") (pinfunction "Gate_1") (pintype "passive"))
      (node (ref "Q3") (pin "3") (pinfunction "Drain_3") (pintype "passive"))
      (node (ref "Q7") (pin "3") (pinfunction "Drain_3") (pintype "passive"))
      (node (ref "Q8") (pin "3") (pinfunction "Drain_3") (pintype "passive"))
      (node (ref "Q9") (pin "3") (pinfunction "Drain_3") (pintype "passive"))
      (node (ref "R25") (pin "1") (pinfunction "1_1") (pintype "passive"))
      (node (ref "R39") (pin "2") (pinfunction "2_2") (pintype "passive"))
    )
    (net (code "74") (name "/Limit_bus") (class "Default")
      (node (ref "J1") (pin "B3") (pinfunction "B3_B3") (pintype "passive"))
      (node (ref "J2") (pin "B3") (pinfunction "B3_B3") (pintype "passive"))
      (node (ref "J3") (pin "B3") (pinfunction "B3_B3") (pintype "passive"))
      (node (ref "J4") (pin "B3") (pinfunction "B3_B3") (pintype "passive"))
      (node (ref "J5") (pin "B3") (pinfunction "B3_B3") (pintype "passive"))
      (node (ref "J6") (pin "B3") (pinfunction "B3_B3") (pintype "passive"))
      (node (ref "R27") (pin "1") (pinfunction "1_1") (pintype "passive"))
      (node (ref "R41") (pin "2") (pinfunction "2_2") (pintype "passive"))
    )
    (net (code "75") (name "/Trigger_bus") (class "Default")
      (node (ref "J1") (pin "B2") (pinfunction "B2_B2") (pintype "passive"))
      (node (ref "J2") (pin "B2") (pinfunction "B2_B2") (pintype "passive"))
      (node (ref "J3") (pin "B2") (pinfunction "B2_B2") (pintype "passive"))
      (node (ref "J4") (pin "B2") (pinfunction "B2_B2") (pintype "passive"))
      (node (ref "J5") (pin "B2") (pinfunction "B2_B2") (pintype "passive"))
      (node (ref "J6") (pin "B2") (pinfunction "B2_B2") (pintype "passive"))
      (node (ref "R26") (pin "1") (pinfunction "1_1") (pintype "passive"))
      (node (ref "R40") (pin "2") (pinfunction "2_2") (pintype "passive"))
    )
    (net (code "77") (name "GND") (class "Default")
      (node (ref "D1") (pin "2") (pinfunction "2_2") (pintype "passive"))
      (node (ref "D10") (pin "2") (pinfunction "2_2") (pintype "passive"))
      (node (ref "D2") (pin "2") (pinfunction "2_2") (pintype "passive"))
      (node (ref "D3") (pin "2") (pinfunction "2_2") (pintype "passive"))
      (node (ref "D4") (pin "2") (pinfunction "2_2") (pintype "passive"))
      (node (ref "D5") (pin "2") (pinfunction "2_2") (pintype "passive"))
      (node (ref "D6") (pin "2") (pinfunction "2_2") (pintype "passive"))
      (node (ref "D9") (pin "2") (pinfunction "2_2") (pintype "passive"))
      (node (ref "J1") (pin "A15") (pinfunction "A15_A15") (pintype "passive"))
      (node (ref "J1") (pin "B15") (pinfunction "B15_B15") (pintype "passive"))
      (node (ref "J10") (pin "2") (pinfunction "2_2") (pintype "passive"))
      (node (ref "J10") (pin "4") (pinfunction "4_4") (pintype "passive"))
      (node (ref "J10") (pin "6") (pinfunction "6_6") (pintype "passive"))
      (node (ref "J11") (pin "2") (pinfunction "2_2") (pintype "passive"))
      (node (ref "J11") (pin "4") (pinfunction "4_4") (pintype "passive"))
      (node (ref "J11") (pin "6") (pinfunction "6_6") (pintype "passive"))
      (node (ref "J12") (pin "2") (pinfunction "2_2") (pintype "passive"))
      (node (ref "J12") (pin "4") (pinfunction "4_4") (pintype "passive"))
      (node (ref "J12") (pin "6") (pinfunction "6_6") (pintype "passive"))
      (node (ref "J2") (pin "A15") (pinfunction "A15_A15") (pintype "passive"))
      (node (ref "J2") (pin "B15") (pinfunction "B15_B15") (pintype "passive"))
      (node (ref "J25") (pin "32") (pinfunction "32_32") (pintype "passive"))
      (node (ref "J25") (pin "34") (pinfunction "34_34") (pintype "passive"))
      (node (ref "J3") (pin "A15") (pinfunction "A15_A15") (pintype "passive"))
      (node (ref "J3") (pin "B15") (pinfunction "B15_B15") (pintype "passive"))
      (node (ref "J4") (pin "A15") (pinfunction "A15_A15") (pintype "passive"))
      (node (ref "J4") (pin "B15") (pinfunction "B15_B15") (pintype "passive"))
      (node (ref "J5") (pin "A15") (pinfunction "A15_A15") (pintype "passive"))
      (node (ref "J5") (pin "B15") (pinfunction "B15_B15") (pintype "passive"))
      (node (ref "J6") (pin "A15") (pinfunction "A15_A15") (pintype "passive"))
      (node (ref "J6") (pin "B15") (pinfunction "B15_B15") (pintype "passive"))
      (node (ref "J7") (pin "2") (pinfunction "2_2") (pintype "passive"))
      (node (ref "J7") (pin "4") (pinfunction "4_4") (pintype "passive"))
      (node (ref "J7") (pin "6") (pinfunction "6_6") (pintype "passive"))
      (node (ref "J8") (pin "2") (pinfunction "2_2") (pintype "passive"))
      (node (ref "J8") (pin "4") (pinfunction "4_4") (pintype "passive"))
      (node (ref "J8") (pin "6") (pinfunction "6_6") (pintype "passive"))
      (node (ref "J9") (pin "2") (pinfunction "2_2") (pintype "passive"))
      (node (ref "J9") (pin "4") (pinfunction "4_4") (pintype "passive"))
      (node (ref "J9") (pin "6") (pinfunction "6_6") (pintype "passive"))
      (node (ref "Q1") (pin "2") (pinfunction "Source_2") (pintype "passive"))
      (node (ref "Q13") (pin "2") (pinfunction "Source_2") (pintype "passive"))
      (node (ref "Q19") (pin "2") (pinfunction "Source_2") (pintype "passive"))
      (node (ref "Q2") (pin "2") (pinfunction "Source_2") (pintype "passive"))
      (node (ref "Q22") (pin "2") (pinfunction "Source_2") (pintype "passive"))
      (node (ref "Q23") (pin "2") (pinfunction "Source_2") (pintype "passive"))
      (node (ref "Q3") (pin "2") (pinfunction "Source_2") (pintype "passive"))
      (node (ref "Q7") (pin "2") (pinfunction "Source_2") (pintype "passive"))
      (node (ref "Q8") (pin "2") (pinfunction "Source_2") (pintype "passive"))
      (node (ref "Q9") (pin "2") (pinfunction "Source_2") (pintype "passive"))
      (node (ref "R39") (pin "1") (pinfunction "1_1") (pintype "passive"))
      (node (ref "R40") (pin "1") (pinfunction "1_1") (pintype "passive"))
      (node (ref "R41") (pin "1") (pinfunction "1_1") (pintype "passive"))
      (node (ref "R42") (pin "1") (pinfunction "1_1") (pintype "passive"))
      (node (ref "R43") (pin "1") (pinfunction "1_1") (pintype "passive"))
      (node (ref "R44") (pin "1") (pinfunction "1_1") (pintype "passive"))
      (node (ref "R45") (pin "1") (pinfunction "1_1") (pintype "passive"))
      (node (ref "R46") (pin "1") (pinfunction "1_1") (pintype "passive"))
      (node (ref "R47") (pin "1") (pinfunction "1_1") (pintype "passive"))
      (node (ref "R48") (pin "1") (pinfunction "1_1") (pintype "passive"))
      (node (ref "R49") (pin "1") (pinfunction "1_1") (pintype "passive"))
      (node (ref "R50") (pin "1") (pinfunction "1_1") (pintype "passive"))
      (node (ref "R51") (pin "1") (pinfunction "1_1") (pintype "passive"))
      (node (ref "R52") (pin "1") (pinfunction "1_1") (pintype "passive"))
      (node (ref "U1") (pin "7") (pinfunction "7_7") (pintype "passive"))
    )
    (net (code "78") (name "Net-(D1-Pad1)") (class "Default")
      (node (ref "D1") (pin "1") (pinfunction "1_1") (pintype "passive"))
      (node (ref "R10") (pin "1") (pinfunction "1_1") (pintype "passive"))
    )
    (net (code "79") (name "Net-(D2-Pad1)") (class "Default")
      (node (ref "D2") (pin "1") (pinfunction "1_1") (pintype "passive"))
      (node (ref "R11") (pin "1") (pinfunction "1_1") (pintype "passive"))
    )
    (net (code "80") (name "Net-(D3-Pad1)") (class "Default")
      (node (ref "D3") (pin "1") (pinfunction "1_1") (pintype "passive"))
      (node (ref "R12") (pin "1") (pinfunction "1_1") (pintype "passive"))
    )
    (net (code "81") (name "Net-(D4-Pad1)") (class "Default")
      (node (ref "D4") (pin "1") (pinfunction "1_1") (pintype "passive"))
      (node (ref "R16") (pin "1") (pinfunction "1_1") (pintype "passive"))
    )
    (net (code "82") (name "Net-(D5-Pad1)") (class "Default")
      (node (ref "D5") (pin "1") (pinfunction "1_1") (pintype "passive"))
      (node (ref "R17") (pin "1") (pinfunction "1_1") (pintype "passive"))
    )
    (net (code "83") (name "Net-(D6-Pad1)") (class "Default")
      (node (ref "D6") (pin "1") (pinfunction "1_1") (pintype "passive"))
      (node (ref "R18") (pin "1") (pinfunction "1_1") (pintype "passive"))
    )
    (net (code "84") (name "Net-(D7-Pad1)") (class "Default")
      (node (ref "D7") (pin "1") (pinfunction "1_1") (pintype "passive"))
      (node (ref "R19") (pin "1") (pinfunction "1_1") (pintype "passive"))
    )
    (net (code "85") (name "Net-(D8-Pad1)") (class "Default")
      (node (ref "D8") (pin "1") (pinfunction "1_1") (pintype "passive"))
      (node (ref "R20") (pin "1") (pinfunction "1_1") (pintype "passive"))
    )
    (net (code "86") (name "Net-(D9-Pad1)") (class "Default")
      (node (ref "D9") (pin "1") (pinfunction "1_1") (pintype "passive"))
      (node (ref "R23") (pin "1") (pinfunction "1_1") (pintype "passive"))
    )
    (net (code "87") (name "Net-(D10-Pad1)") (class "Default")
      (node (ref "D10") (pin "1") (pinfunction "1_1") (pintype "passive"))
      (node (ref "R24") (pin "1") (pinfunction "1_1") (pintype "passive"))
    )
    (net (code "88") (name "Net-(J1-PadA11)") (class "Default")
      (node (ref "J1") (pin "A11") (pinfunction "A11_A11") (pintype "passive"))
      (node (ref "J13") (pin "1") (pinfunction "1_1") (pintype "passive"))
    )
    (net (code "89") (name "Net-(J1-PadA12)") (class "Default")
      (node (ref "J1") (pin "A12") (pinfunction "A12_A12") (pintype "passive"))
      (node (ref "J13") (pin "2") (pinfunction "2_2") (pintype "passive"))
    )
    (net (code "90") (name "Net-(J1-PadA13)") (class "Default")
      (node (ref "J1") (pin "A13") (pinfunction "A13_A13") (pintype "passive"))
      (node (ref "J14") (pin "1") (pinfunction "1_1") (pintype "passive"))
    )
    (net (code "91") (name "Net-(J1-PadA14)") (class "Default")
      (node (ref "J1") (pin "A14") (pinfunction "A14_A14") (pintype "passive"))
      (node (ref "J14") (pin "2") (pinfunction "2_2") (pintype "passive"))
    )
    (net (code "92") (name "Net-(J15-Pad1)") (class "Default")
      (node (ref "J15") (pin "1") (pinfunction "1_1") (pintype "passive"))
      (node (ref "J2") (pin "A11") (pinfunction "A11_A11") (pintype "passive"))
    )
    (net (code "93") (name "Net-(J15-Pad2)") (class "Default")
      (node (ref "J15") (pin "2") (pinfunction "2_2") (pintype "passive"))
      (node (ref "J2") (pin "A12") (pinfunction "A12_A12") (pintype "passive"))
    )
    (net (code "94") (name "Net-(J16-Pad1)") (class "Default")
      (node (ref "J16") (pin "1") (pinfunction "1_1") (pintype "passive"))
      (node (ref "J2") (pin "A13") (pinfunction "A13_A13") (pintype "passive"))
    )
    (net (code "95") (name "Net-(J16-Pad2)") (class "Default")
      (node (ref "J16") (pin "2") (pinfunction "2_2") (pintype "passive"))
      (node (ref "J2") (pin "A14") (pinfunction "A14_A14") (pintype "passive"))
    )
    (net (code "96") (name "Net-(J17-Pad1)") (class "Default")
      (node (ref "J17") (pin "1") (pinfunction "1_1") (pintype "passive"))
      (node (ref "J3") (pin "A11") (pinfunction "A11_A11") (pintype "passive"))
    )
    (net (code "97") (name "Net-(J17-Pad2)") (class "Default")
      (node (ref "J17") (pin "2") (pinfunction "2_2") (pintype "passive"))
      (node (ref "J3") (pin "A12") (pinfunction "A12_A12") (pintype "passive"))
    )
    (net (code "98") (name "Net-(J18-Pad1)") (class "Default")
      (node (ref "J18") (pin "1") (pinfunction "1_1") (pintype "passive"))
      (node (ref "J3") (pin "A13") (pinfunction "A13_A13") (pintype "passive"))
    )
    (net (code "99") (name "Net-(J18-Pad2)") (class "Default")
      (node (ref "J18") (pin "2") (pinfunction "2_2") (pintype "passive"))
      (node (ref "J3") (pin "A14") (pinfunction "A14_A14") (pintype "passive"))
    )
    (net (code "100") (name "Net-(J19-Pad1)") (class "Default")
      (node (ref "J19") (pin "1") (pinfunction "1_1") (pintype "passive"))
      (node (ref "J4") (pin "A11") (pinfunction "A11_A11") (pintype "passive"))
    )
    (net (code "101") (name "Net-(J19-Pad2)") (class "Default")
      (node (ref "J19") (pin "2") (pinfunction "2_2") (pintype "passive"))
      (node (ref "J4") (pin "A12") (pinfunction "A12_A12") (pintype "passive"))
    )
    (net (code "102") (name "Net-(J20-Pad1)") (class "Default")
      (node (ref "J20") (pin "1") (pinfunction "1_1") (pintype "passive"))
      (node (ref "J4") (pin "A13") (pinfunction "A13_A13") (pintype "passive"))
    )
    (net (code "103") (name "Net-(J20-Pad2)") (class "Default")
      (node (ref "J20") (pin "2") (pinfunction "2_2") (pintype "passive"))
      (node (ref "J4") (pin "A14") (pinfunction "A14_A14") (pintype "passive"))
    )
    (net (code "104") (name "Net-(J21-Pad1)") (class "Default")
      (node (ref "J21") (pin "1") (pinfunction "1_1") (pintype "passive"))
      (node (ref "J5") (pin "A11") (pinfunction "A11_A11") (pintype "passive"))
    )
    (net (code "105") (name "Net-(J21-Pad2)") (class "Default")
      (node (ref "J21") (pin "2") (pinfunction "2_2") (pintype "passive"))
      (node (ref "J5") (pin "A12") (pinfunction "A12_A12") (pintype "passive"))
    )
    (net (code "106") (name "Net-(J22-Pad1)") (class "Default")
      (node (ref "J22") (pin "1") (pinfunction "1_1") (pintype "passive"))
      (node (ref "J5") (pin "A13") (pinfunction "A13_A13") (pintype "passive"))
    )
    (net (code "107") (name "Net-(J22-Pad2)") (class "Default")
      (node (ref "J22") (pin "2") (pinfunction "2_2") (pintype "passive"))
      (node (ref "J5") (pin "A14") (pinfunction "A14_A14") (pintype "passive"))
    )
    (net (code "108") (name "Net-(J23-Pad1)") (class "Default")
      (node (ref "J23") (pin "1") (pinfunction "1_1") (pintype "passive"))
      (node (ref "J6") (pin "A11") (pinfunction "A11_A11") (pintype "passive"))
    )
    (net (code "109") (name "Net-(J23-Pad2)") (class "Default")
      (node (ref "J23") (pin "2") (pinfunction "2_2") (pintype "passive"))
      (node (ref "J6") (pin "A12") (pinfunction "A12_A12") (pintype "passive"))
    )
    (net (code "110") (name "Net-(J24-Pad1)") (class "Default")
      (node (ref "J24") (pin "1") (pinfunction "1_1") (pintype "passive"))
      (node (ref "J6") (pin "A13") (pinfunction "A13_A13") (pintype "passive"))
    )
    (net (code "111") (name "Net-(J24-Pad2)") (class "Default")
      (node (ref "J24") (pin "2") (pinfunction "2_2") (pintype "passive"))
      (node (ref "J6") (pin "A14") (pinfunction "A14_A14") (pintype "passive"))
    )
    (net (code "112") (name "Net-(J26-Pad1)") (class "Default")
      (node (ref "J26") (pin "1") (pinfunction "1_1") (pintype "passive"))
      (node (ref "R22") (pin "1") (pinfunction "1_1") (pintype "passive"))
    )
    (net (code "113") (name "Net-(J26-Pad2)") (class "Default")
      (node (ref "J26") (pin "2") (pinfunction "2_2") (pintype "passive"))
      (node (ref "U1") (pin "2") (pinfunction "2_2") (pintype "passive"))
    )
    (net (code "114") (name "Net-(Q1-Gate)") (class "Default")
      (node (ref "J1") (pin "A1") (pinfunction "A1_A1") (pintype "passive"))
      (node (ref "Q1") (pin "1") (pinfunction "Gate_1") (pintype "passive"))
      (node (ref "Q4") (pin "1") (pinfunction "Gate_1") (pintype "passive"))
      (node (ref "R7") (pin "1") (pinfunction "1_1") (pintype "passive"))
    )
    (net (code "115") (name "Net-(Q2-Gate)") (class "Default")
      (node (ref "J2") (pin "A1") (pinfunction "A1_A1") (pintype "passive"))
      (node (ref "Q2") (pin "1") (pinfunction "Gate_1") (pintype "passive"))
      (node (ref "Q5") (pin "1") (pinfunction "Gate_1") (pintype "passive"))
      (node (ref "R8") (pin "1") (pinfunction "1_1") (pintype "passive"))
    )
    (net (code "116") (name "Net-(Q3-Gate)") (class "Default")
      (node (ref "J3") (pin "A1") (pinfunction "A1_A1") (pintype "passive"))
      (node (ref "Q3") (pin "1") (pinfunction "Gate_1") (pintype "passive"))
      (node (ref "Q6") (pin "1") (pinfunction "Gate_1") (pintype "passive"))
      (node (ref "R9") (pin "1") (pinfunction "1_1") (pintype "passive"))
    )
    (net (code "117") (name "Net-(Q10-Gate)") (class "Default")
      (node (ref "J4") (pin "A1") (pinfunction "A1_A1") (pintype "passive"))
      (node (ref "Q10") (pin "1") (pinfunction "Gate_1") (pintype "passive"))
      (node (ref "Q7") (pin "1") (pinfunction "Gate_1") (pintype "passive"))
      (node (ref "R13") (pin "1") (pinfunction "1_1") (pintype "passive"))
    )
    (net (code "118") (name "Net-(Q11-Gate)") (class "Default")
      (node (ref "J5") (pin "A1") (pinfunction "A1_A1") (pintype "passive"))
      (node (ref "Q11") (pin "1") (pinfunction "Gate_1") (pintype "passive"))
      (node (ref "Q8") (pin "1") (pinfunction "Gate_1") (pintype "passive"))
      (node (ref "R14") (pin "1") (pinfunction "1_1") (pintype "passive"))
    )
    (net (code "119") (name "Net-(Q12-Gate)") (class "Default")
      (node (ref "J6") (pin "A1") (pinfunction "A1_A1") (pintype "passive"))
      (node (ref "Q12") (pin "1") (pinfunction "Gate_1") (pintype "passive"))
      (node (ref "Q9") (pin "1") (pinfunction "Gate_1") (pintype "passive"))
      (node (ref "R15") (pin "1") (pinfunction "1_1") (pintype "passive"))
    )
    (net (code "120") (name "Net-(Q13-Gate)") (class "Default")
      (node (ref "Q13") (pin "1") (pinfunction "Gate_1") (pintype "passive"))
      (node (ref "Q20") (pin "1") (pinfunction "Gate_1") (pintype "passive"))
      (node (ref "Q22") (pin "1") (pinfunction "Gate_1") (pintype "passive"))
      (node (ref "R21") (pin "1") (pinfunction "1_1") (pintype "passive"))
      (node (ref "U1") (pin "8") (pinfunction "8_8") (pintype "passive"))
    )
    (net (code "121") (name "Net-(Q19-Drain)") (class "Default")
      (node (ref "J27") (pin "2") (pinfunction "2_2") (pintype "passive"))
      (node (ref "Q19") (pin "3") (pinfunction "Drain_3") (pintype "passive"))
    )
    (net (code "122") (name "Net-(Q20-Drain)") (class "Default")
      (node (ref "Q20") (pin "3") (pinfunction "Drain_3") (pintype "passive"))
      (node (ref "R23") (pin "2") (pinfunction "2_2") (pintype "passive"))
    )
    (net (code "123") (name "Net-(Q21-Drain)") (class "Default")
      (node (ref "Q21") (pin "3") (pinfunction "Drain_3") (pintype "passive"))
      (node (ref "R24") (pin "2") (pinfunction "2_2") (pintype "passive"))
    )
    (net (code "124") (name "Net-(Q22-Drain)") (class "Default")
      (node (ref "D7") (pin "2") (pinfunction "2_2") (pintype "passive"))
      (node (ref "Q22") (pin "3") (pinfunction "Drain_3") (pintype "passive"))
    )
    (net (code "125") (name "Net-(Q23-Drain)") (class "Default")
      (node (ref "D8") (pin "2") (pinfunction "2_2") (pintype "passive"))
      (node (ref "Q23") (pin "3") (pinfunction "Drain_3") (pintype "passive"))
    )
    (net (code "126") (name "Net-(R22-Pad2)") (class "Default")
      (node (ref "R22") (pin "2") (pinfunction "2_2") (pintype "passive"))
      (node (ref "U1") (pin "1") (pinfunction "1_1") (pintype "passive"))
    )
    (net (code "127") (name "VCC_Extra") (class "Default")
      (node (ref "J1") (pin "A16") (pinfunction "A16_A16") (pintype "passive"))
      (node (ref "J1") (pin "B16") (pinfunction "B16_B16") (pintype "passive"))
      (node (ref "J2") (pin "A16") (pinfunction "A16_A16") (pintype "passive"))
      (node (ref "J2") (pin "B16") (pinfunction "B16_B16") (pintype "passive"))
      (node (ref "J3") (pin "A16") (pinfunction "A16_A16") (pintype "passive"))
      (node (ref "J3") (pin "B16") (pinfunction "B16_B16") (pintype "passive"))
      (node (ref "J4") (pin "A16") (pinfunction "A16_A16") (pintype "passive"))
      (node (ref "J4") (pin "B16") (pinfunction "B16_B16") (pintype "passive"))
      (node (ref "J5") (pin "A16") (pinfunction "A16_A16") (pintype "passive"))
      (node (ref "J5") (pin "B16") (pinfunction "B16_B16") (pintype "passive"))
      (node (ref "J6") (pin "A16") (pinfunction "A16_A16") (pintype "passive"))
      (node (ref "J6") (pin "B16") (pinfunction "B16_B16") (pintype "passive"))
    )
    (net (code "128") (name "VCC_P5V0") (class "Default")
      (node (ref "J1") (pin "A17") (pinfunction "A17_A17") (pintype "passive"))
      (node (ref "J1") (pin "B17") (pinfunction "B17_B17") (pintype "passive"))
      (node (ref "J10") (pin "10") (pinfunction "10_10") (pintype "passive"))
      (node (ref "J10") (pin "8") (pinfunction "8_8") (pintype "passive"))
      (node (ref "J11") (pin "10") (pinfunction "10_10") (pintype "passive"))
      (node (ref "J11") (pin "8") (pinfunction "8_8") (pintype "passive"))
      (node (ref "J12") (pin "10") (pinfunction "10_10") (pintype "passive"))
      (node (ref "J12") (pin "8") (pinfunction "8_8") (pintype "passive"))
      (node (ref "J2") (pin "A17") (pinfunction "A17_A17") (pintype "passive"))
      (node (ref "J2") (pin "B17") (pinfunction "B17_B17") (pintype "passive"))
      (node (ref "J25") (pin "31") (pinfunction "31_31") (pintype "passive"))
      (node (ref "J25") (pin "33") (pinfunction "33_33") (pintype "passive"))
      (node (ref "J27") (pin "1") (pinfunction "1_1") (pintype "passive"))
      (node (ref "J3") (pin "A17") (pinfunction "A17_A17") (pintype "passive"))
      (node (ref "J3") (pin "B17") (pinfunction "B17_B17") (pintype "passive"))
      (node (ref "J4") (pin "A17") (pinfunction "A17_A17") (pintype "passive"))
      (node (ref "J4") (pin "B17") (pinfunction "B17_B17") (pintype "passive"))
      (node (ref "J5") (pin "A17") (pinfunction "A17_A17") (pintype "passive"))
      (node (ref "J5") (pin "B17") (pinfunction "B17_B17") (pintype "passive"))
      (node (ref "J6") (pin "A17") (pinfunction "A17_A17") (pintype "passive"))
      (node (ref "J6") (pin "B17") (pinfunction "B17_B17") (pintype "passive"))
      (node (ref "J7") (pin "10") (pinfunction "10_10") (pintype "passive"))
      (node (ref "J7") (pin "8") (pinfunction "8_8") (pintype "passive"))
      (node (ref "J8") (pin "10") (pinfunction "10_10") (pintype "passive"))
      (node (ref "J8") (pin "8") (pinfunction "8_8") (pintype "passive"))
      (node (ref "J9") (pin "10") (pinfunction "10_10") (pintype "passive"))
      (node (ref "J9") (pin "8") (pinfunction "8_8") (pintype "passive"))
      (node (ref "Q10") (pin "2") (pinfunction "Source_2") (pintype "passive"))
      (node (ref "Q11") (pin "2") (pinfunction "Source_2") (pintype "passive"))
      (node (ref "Q12") (pin "2") (pinfunction "Source_2") (pintype "passive"))
      (node (ref "Q20") (pin "2") (pinfunction "Source_2") (pintype "passive"))
      (node (ref "Q21") (pin "2") (pinfunction "Source_2") (pintype "passive"))
      (node (ref "Q4") (pin "2") (pinfunction "Source_2") (pintype "passive"))
      (node (ref "Q5") (pin "2") (pinfunction "Source_2") (pintype "passive"))
      (node (ref "Q6") (pin "2") (pinfunction "Source_2") (pintype "passive"))
      (node (ref "R13") (pin "2") (pinfunction "2_2") (pintype "passive"))
      (node (ref "R14") (pin "2") (pinfunction "2_2") (pintype "passive"))
      (node (ref "R15") (pin "2") (pinfunction "2_2") (pintype "passive"))
      (node (ref "R19") (pin "2") (pinfunction "2_2") (pintype "passive"))
      (node (ref "R20") (pin "2") (pinfunction "2_2") (pintype "passive"))
      (node (ref "R21") (pin "2") (pinfunction "2_2") (pintype "passive"))
      (node (ref "R25") (pin "2") (pinfunction "2_2") (pintype "passive"))
      (node (ref "R26") (pin "2") (pinfunction "2_2") (pintype "passive"))
      (node (ref "R27") (pin "2") (pinfunction "2_2") (pintype "passive"))
      (node (ref "R28") (pin "2") (pinfunction "2_2") (pintype "passive"))
      (node (ref "R29") (pin "2") (pinfunction "2_2") (pintype "passive"))
      (node (ref "R30") (pin "2") (pinfunction "2_2") (pintype "passive"))
      (node (ref "R31") (pin "2") (pinfunction "2_2") (pintype "passive"))
      (node (ref "R32") (pin "2") (pinfunction "2_2") (pintype "passive"))
      (node (ref "R33") (pin "2") (pinfunction "2_2") (pintype "passive"))
      (node (ref "R34") (pin "2") (pinfunction "2_2") (pintype "passive"))
      (node (ref "R35") (pin "2") (pinfunction "2_2") (pintype "passive"))
      (node (ref "R36") (pin "2") (pinfunction "2_2") (pintype "passive"))
      (node (ref "R37") (pin "2") (pinfunction "2_2") (pintype "passive"))
      (node (ref "R38") (pin "2") (pinfunction "2_2") (pintype "passive"))
      (node (ref "R7") (pin "2") (pinfunction "2_2") (pintype "passive"))
      (node (ref "R8") (pin "2") (pinfunction "2_2") (pintype "passive"))
      (node (ref "R9") (pin "2") (pinfunction "2_2") (pintype "passive"))
    )
    (net (code "129") (name "VCC_P18V") (class "Default")
      (node (ref "J1") (pin "A18") (pinfunction "A18_A18") (pintype "passive"))
      (node (ref "J1") (pin "B18") (pinfunction "B18_B18") (pintype "passive"))
      (node (ref "J2") (pin "A18") (pinfunction "A18_A18") (pintype "passive"))
      (node (ref "J2") (pin "B18") (pinfunction "B18_B18") (pintype "passive"))
      (node (ref "J3") (pin "A18") (pinfunction "A18_A18") (pintype "passive"))
      (node (ref "J3") (pin "B18") (pinfunction "B18_B18") (pintype "passive"))
      (node (ref "J4") (pin "A18") (pinfunction "A18_A18") (pintype "passive"))
      (node (ref "J4") (pin "B18") (pinfunction "B18_B18") (pintype "passive"))
      (node (ref "J5") (pin "A18") (pinfunction "A18_A18") (pintype "passive"))
      (node (ref "J5") (pin "B18") (pinfunction "B18_B18") (pintype "passive"))
      (node (ref "J6") (pin "A18") (pinfunction "A18_A18") (pintype "passive"))
      (node (ref "J6") (pin "B18") (pinfunction "B18_B18") (pintype "passive"))
    )
    (net (code "130") (name "unconnected-(U1-Pad3)") (class "Default")
      (node (ref "U1") (pin "3") (pinfunction "3_3") (pintype "passive"))
    )
    (net (code "131") (name "unconnected-(U1-Pad4)") (class "Default")
      (node (ref "U1") (pin "4") (pinfunction "4_4") (pintype "passive"))
    )
    (net (code "132") (name "unconnected-(U1-Pad5)") (class "Default")
      (node (ref "U1") (pin "5") (pinfunction "5_5") (pintype "passive"))
    )
    (net (code "133") (name "unconnected-(U1-Pad6)") (class "Default")
      (node (ref "U1") (pin "6") (pinfunction "6_6") (pintype "passive"))
    )
  )
)
